# skematik.net
KiCad netlist of a schematic drawn in EAGLE
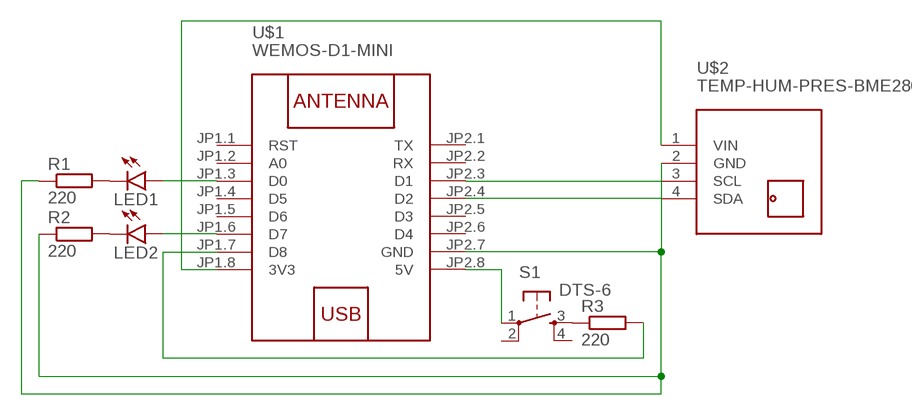
[diagram p0: schematic, sheet 1]

(export (version "E")
  (design (tool "Eeschema 10.0.6"))
  (components
    (comp (ref "LED1")
      (value "LED")
      (footprint "eagle-import:SMARTLED-TTW")
      (libsource (lib "eagle-import") (part "LED"))
    )
    (comp (ref "LED2")
      (value "LED")
      (footprint "eagle-import:SMARTLED-TTW")
      (libsource (lib "eagle-import") (part "LED"))
    )
    (comp (ref "R1")
      (value "220")
      (footprint "eagle-import:0207_10")
      (libsource (lib "eagle-import") (part "R-EU_0207/10"))
    )
    (comp (ref "R2")
      (value "220")
      (footprint "eagle-import:0207_10")
      (libsource (lib "eagle-import") (part "R-EU_0207/10"))
    )
    (comp (ref "R3")
      (value "220")
      (footprint "eagle-import:0207_10")
      (libsource (lib "eagle-import") (part "R-EU_0207/10"))
    )
    (comp (ref "S1")
      (value "DTS-6")
      (footprint "eagle-import:DTS-6")
      (libsource (lib "eagle-import") (part "DTS-6"))
    )
    (comp (ref "U$1")
      (value "WEMOS-D1-MINI")
      (footprint "eagle-import:WEMOS-D1-MINI")
      (libsource (lib "eagle-import") (part "WEMOS-D1-MINI"))
    )
    (comp (ref "U$2")
      (value "TEMP-HUM-PRES-BME280")
      (footprint "eagle-import:TEMP-HUM-PRES-BME280")
      (libsource (lib "eagle-import") (part "TEMP-HUM-PRES-BME280"))
    )
  )
  (nets
    (net (code "1") (name "Net-(LED1-A)") (class "Default")
      (node (ref "LED1") (pin "A@1") (pinfunction "A_A@1") (pintype "passive"))
      (node (ref "U$1") (pin "JP1.3") (pinfunction "D0_JP1.3") (pintype "bidirectional"))
    )
    (net (code "2") (name "Net-(LED1-C)") (class "Default")
      (node (ref "LED1") (pin "C@1") (pinfunction "C_C@1") (pintype "passive"))
      (node (ref "R1") (pin "2") (pinfunction "2_2") (pintype "passive"))
    )
    (net (code "3") (name "Net-(LED2-A)") (class "Default")
      (node (ref "LED2") (pin "A@1") (pinfunction "A_A@1") (pintype "passive"))
      (node (ref "U$1") (pin "JP1.6") (pinfunction "D7_JP1.6") (pintype "bidirectional"))
    )
    (net (code "4") (name "Net-(LED2-C)") (class "Default")
      (node (ref "LED2") (pin "C@1") (pinfunction "C_C@1") (pintype "passive"))
      (node (ref "R2") (pin "2") (pinfunction "2_2") (pintype "passive"))
    )
    (net (code "5") (name "Net-(R3-Pad1)") (class "Default")
      (node (ref "R3") (pin "1") (pinfunction "1_1") (pintype "passive"))
      (node (ref "S1") (pin "3") (pinfunction "3_3") (pintype "passive"))
    )
    (net (code "6") (name "Net-(U$1-3V3)") (class "Default")
      (node (ref "U$1") (pin "JP1.8") (pinfunction "3V3_JP1.8") (pintype "power_in"))
      (node (ref "U$2") (pin "1") (pinfunction "VIN_1") (pintype "power_in"))
    )
    (net (code "7") (name "Net-(U$1-5V)") (class "Default")
      (node (ref "S1") (pin "1") (pinfunction "1_1") (pintype "passive"))
      (node (ref "U$1") (pin "JP2.8") (pinfunction "5V_JP2.8") (pintype "power_in"))
    )
    (net (code "8") (name "Net-(U$1-D1)") (class "Default")
      (node (ref "U$1") (pin "JP2.3") (pinfunction "D1_JP2.3") (pintype "bidirectional"))
      (node (ref "U$2") (pin "3") (pinfunction "SCL_3") (pintype "bidirectional"))
    )
    (net (code "9") (name "Net-(U$1-D2)") (class "Default")
      (node (ref "U$1") (pin "JP2.4") (pinfunction "D2_JP2.4") (pintype "bidirectional"))
      (node (ref "U$2") (pin "4") (pinfunction "SDA_4") (pintype "bidirectional"))
    )
    (net (code "10") (name "Net-(U$1-D8)") (class "Default")
      (node (ref "R3") (pin "2") (pinfunction "2_2") (pintype "passive"))
      (node (ref "U$1") (pin "JP1.7") (pinfunction "D8_JP1.7") (pintype "bidirectional"))
    )
    (net (code "11") (name "Net-(U$1-GND)") (class "Default")
      (node (ref "R1") (pin "1") (pinfunction "1_1") (pintype "passive"))
      (node (ref "R2") (pin "1") (pinfunction "1_1") (pintype "passive"))
      (node (ref "U$1") (pin "JP2.7") (pinfunction "GND_JP2.7") (pintype "power_in"))
      (node (ref "U$2") (pin "2") (pinfunction "GND_2") (pintype "power_in"))
    )
    (net (code "12") (name "unconnected-(S1-Pad2)") (class "Default")
      (node (ref "S1") (pin "2") (pinfunction "2_2") (pintype "passive"))
    )
    (net (code "13") (name "unconnected-(S1-Pad4)") (class "Default")
      (node (ref "S1") (pin "4") (pinfunction "4_4") (pintype "passive"))
    )
    (net (code "14") (name "unconnected-(U$1-A0-PadJP1.2)") (class "Default")
      (node (ref "U$1") (pin "JP1.2") (pinfunction "A0_JP1.2") (pintype "bidirectional"))
    )
    (net (code "15") (name "unconnected-(U$1-D3-PadJP2.5)") (class "Default")
      (node (ref "U$1") (pin "JP2.5") (pinfunction "D3_JP2.5") (pintype "bidirectional"))
    )
    (net (code "16") (name "unconnected-(U$1-D4-PadJP2.6)") (class "Default")
      (node (ref "U$1") (pin "JP2.6") (pinfunction "D4_JP2.6") (pintype "bidirectional"))
    )
    (net (code "17") (name "unconnected-(U$1-D5-PadJP1.4)") (class "Default")
      (node (ref "U$1") (pin "JP1.4") (pinfunction "D5_JP1.4") (pintype "bidirectional"))
    )
    (net (code "18") (name "unconnected-(U$1-D6-PadJP1.5)") (class "Default")
      (node (ref "U$1") (pin "JP1.5") (pinfunction "D6_JP1.5") (pintype "bidirectional"))
    )
    (net (code "19") (name "unconnected-(U$1-RST-PadJP1.1)") (class "Default")
      (node (ref "U$1") (pin "JP1.1") (pinfunction "RST_JP1.1") (pintype "bidirectional"))
    )
    (net (code "20") (name "unconnected-(U$1-RX-PadJP2.2)") (class "Default")
      (node (ref "U$1") (pin "JP2.2") (pinfunction "RX_JP2.2") (pintype "bidirectional"))
    )
    (net (code "21") (name "unconnected-(U$1-TX-PadJP2.1)") (class "Default")
      (node (ref "U$1") (pin "JP2.1") (pinfunction "TX_JP2.1") (pintype "bidirectional"))
    )
  )
)
